# CacheMakerUno.net
KiCad netlist of a schematic drawn in EAGLE
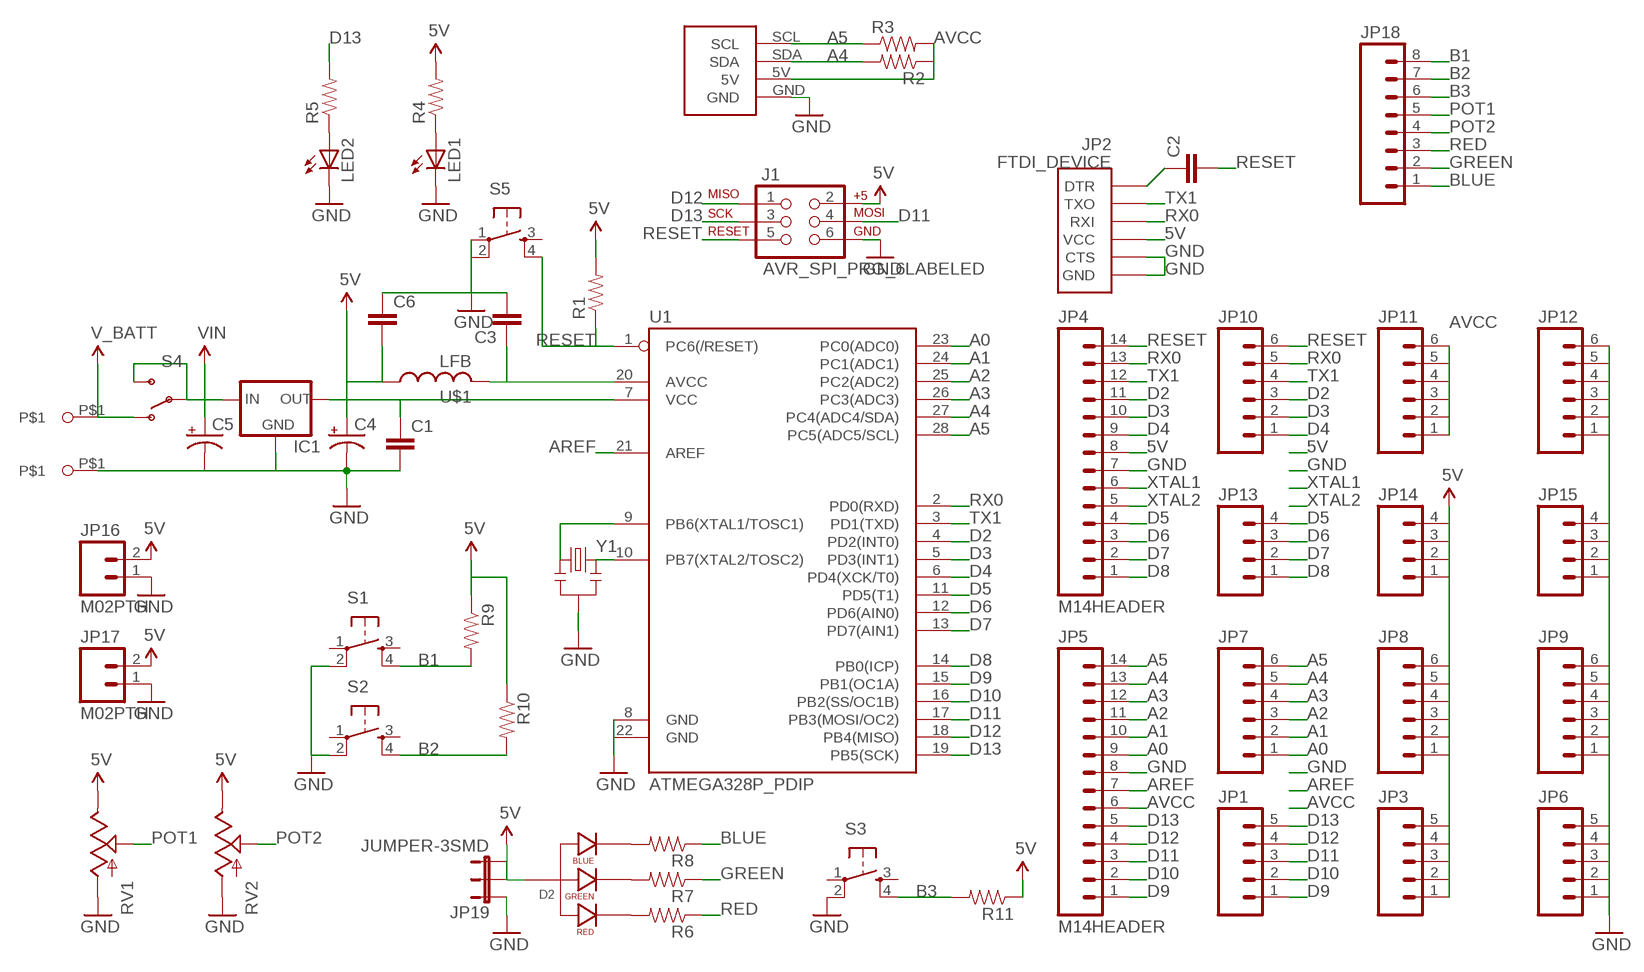
[diagram p0: schematic, sheet 1]

(export (version "E")
  (design (tool "Eeschema 10.0.6"))
  (components
    (comp (ref "C1")
      (value "CAPPTH")
      (footprint "eagle-import:CAP-PTH-SMALL")
      (libsource (lib "eagle-import") (part "CAPPTH"))
    )
    (comp (ref "C2")
      (value "CAPPTH")
      (footprint "eagle-import:CAP-PTH-SMALL")
      (libsource (lib "eagle-import") (part "CAPPTH"))
    )
    (comp (ref "C3")
      (value "CAPPTH")
      (footprint "eagle-import:CAP-PTH-SMALL")
      (libsource (lib "eagle-import") (part "CAPPTH"))
    )
    (comp (ref "C4")
      (value "CAP_POL2MM")
      (footprint "eagle-import:CAP-PTH-2MM")
      (libsource (lib "eagle-import") (part "CAP_POL2MM"))
    )
    (comp (ref "C5")
      (value "CAP_POL2MM")
      (footprint "eagle-import:CAP-PTH-2MM")
      (libsource (lib "eagle-import") (part "CAP_POL2MM"))
    )
    (comp (ref "C6")
      (value "CAPPTH")
      (footprint "eagle-import:CAP-PTH-SMALL")
      (libsource (lib "eagle-import") (part "CAPPTH"))
    )
    (comp (ref "D2")
      (value "LED-RGB-CA-THRUDIFFUSE")
      (footprint "eagle-import:LED-RGB-THRU")
      (libsource (lib "eagle-import") (part "LED-RGB-CA-THRUDIFFUSE"))
    )
    (comp (ref "GND")
      (value "M1")
      (footprint "eagle-import:M1_NO_STRAIN")
      (libsource (lib "eagle-import") (part "M1"))
    )
    (comp (ref "IC1")
      (value "V_REG_78XXBASIC")
      (footprint "eagle-import:TO-220-REG-BASIC")
      (libsource (lib "eagle-import") (part "V_REG_78XXBASIC"))
    )
    (comp (ref "J1")
      (value "AVR_SPI_PRG_6LABELED")
      (footprint "eagle-import:2X3-NS")
      (libsource (lib "eagle-import") (part "AVR_SPI_PRG_6LABELED"))
    )
    (comp (ref "JP1")
      (value "M05NO_SILK")
      (footprint "eagle-import:1X05_NO_SILK")
      (libsource (lib "eagle-import") (part "M05NO_SILK"))
    )
    (comp (ref "JP2")
      (value "FTDI_DEVICE")
      (footprint "eagle-import:FTDI_DEVICE_SIDE")
      (libsource (lib "eagle-import") (part "FTDI_DEVICE"))
    )
    (comp (ref "JP3")
      (value "M05NO_SILK")
      (footprint "eagle-import:1X05_NO_SILK")
      (libsource (lib "eagle-import") (part "M05NO_SILK"))
    )
    (comp (ref "JP4")
      (value "M14HEADER")
      (footprint "eagle-import:1X14-HEADER")
      (libsource (lib "eagle-import") (part "M14HEADER"))
    )
    (comp (ref "JP5")
      (value "M14HEADER")
      (footprint "eagle-import:1X14-HEADER")
      (libsource (lib "eagle-import") (part "M14HEADER"))
    )
    (comp (ref "JP6")
      (value "M05NO_SILK")
      (footprint "eagle-import:1X05_NO_SILK")
      (libsource (lib "eagle-import") (part "M05NO_SILK"))
    )
    (comp (ref "JP7")
      (value "M06SIP")
      (footprint "eagle-import:1X06")
      (libsource (lib "eagle-import") (part "M06SIP"))
    )
    (comp (ref "JP8")
      (value "M06SIP")
      (footprint "eagle-import:1X06")
      (libsource (lib "eagle-import") (part "M06SIP"))
    )
    (comp (ref "JP9")
      (value "M06SIP")
      (footprint "eagle-import:1X06")
      (libsource (lib "eagle-import") (part "M06SIP"))
    )
    (comp (ref "JP10")
      (value "M06SIP")
      (footprint "eagle-import:1X06")
      (libsource (lib "eagle-import") (part "M06SIP"))
    )
    (comp (ref "JP11")
      (value "M06SIP")
      (footprint "eagle-import:1X06")
      (libsource (lib "eagle-import") (part "M06SIP"))
    )
    (comp (ref "JP12")
      (value "M06SIP")
      (footprint "eagle-import:1X06")
      (libsource (lib "eagle-import") (part "M06SIP"))
    )
    (comp (ref "JP13")
      (value "M04PTH")
      (footprint "eagle-import:1X04")
      (libsource (lib "eagle-import") (part "M04PTH"))
    )
    (comp (ref "JP14")
      (value "M04PTH")
      (footprint "eagle-import:1X04")
      (libsource (lib "eagle-import") (part "M04PTH"))
    )
    (comp (ref "JP15")
      (value "M04PTH")
      (footprint "eagle-import:1X04")
      (libsource (lib "eagle-import") (part "M04PTH"))
    )
    (comp (ref "JP16")
      (value "M02PTH")
      (footprint "eagle-import:1X02")
      (libsource (lib "eagle-import") (part "M02PTH"))
    )
    (comp (ref "JP17")
      (value "M02PTH")
      (footprint "eagle-import:1X02")
      (libsource (lib "eagle-import") (part "M02PTH"))
    )
    (comp (ref "JP18")
      (value "M081X08")
      (footprint "eagle-import:1X08")
      (libsource (lib "eagle-import") (part "M081X08"))
    )
    (comp (ref "JP19")
      (value "JUMPER-3SMD")
      (footprint "eagle-import:SJ_3")
      (libsource (lib "eagle-import") (part "JUMPER-3SMD"))
    )
    (comp (ref "LED1")
      (value "LED5MM")
      (footprint "eagle-import:LED5MM")
      (libsource (lib "eagle-import") (part "LED5MM"))
    )
    (comp (ref "LED2")
      (value "LED5MM")
      (footprint "eagle-import:LED5MM")
      (libsource (lib "eagle-import") (part "LED5MM"))
    )
    (comp (ref "R1")
      (value "RESISTORAXIAL-0.3")
      (footprint "eagle-import:AXIAL-0.3")
      (libsource (lib "eagle-import") (part "RESISTORAXIAL-0.3"))
    )
    (comp (ref "R2")
      (value "RESISTORAXIAL-0.3")
      (footprint "eagle-import:AXIAL-0.3")
      (libsource (lib "eagle-import") (part "RESISTORAXIAL-0.3"))
    )
    (comp (ref "R3")
      (value "RESISTORAXIAL-0.3")
      (footprint "eagle-import:AXIAL-0.3")
      (libsource (lib "eagle-import") (part "RESISTORAXIAL-0.3"))
    )
    (comp (ref "R4")
      (value "RESISTORPTH-1/4W-VERT")
      (footprint "eagle-import:AXIAL-0.1")
      (libsource (lib "eagle-import") (part "RESISTORPTH-1/4W-VERT"))
    )
    (comp (ref "R5")
      (value "RESISTORAXIAL-0.3")
      (footprint "eagle-import:AXIAL-0.3")
      (libsource (lib "eagle-import") (part "RESISTORAXIAL-0.3"))
    )
    (comp (ref "R6")
      (value "RESISTORPTH-1/4W-VERT")
      (footprint "eagle-import:AXIAL-0.1")
      (libsource (lib "eagle-import") (part "RESISTORPTH-1/4W-VERT"))
    )
    (comp (ref "R7")
      (value "RESISTORPTH-1/4W-VERT")
      (footprint "eagle-import:AXIAL-0.1")
      (libsource (lib "eagle-import") (part "RESISTORPTH-1/4W-VERT"))
    )
    (comp (ref "R8")
      (value "RESISTORPTH-1/4W-VERT")
      (footprint "eagle-import:AXIAL-0.1")
      (libsource (lib "eagle-import") (part "RESISTORPTH-1/4W-VERT"))
    )
    (comp (ref "R9")
      (value "RESISTORPTH-1/4W-VERT")
      (footprint "eagle-import:AXIAL-0.1")
      (libsource (lib "eagle-import") (part "RESISTORPTH-1/4W-VERT"))
    )
    (comp (ref "R10")
      (value "RESISTORPTH-1/4W-VERT")
      (footprint "eagle-import:AXIAL-0.1")
      (libsource (lib "eagle-import") (part "RESISTORPTH-1/4W-VERT"))
    )
    (comp (ref "R11")
      (value "RESISTORPTH-1/4W-VERT")
      (footprint "eagle-import:AXIAL-0.1")
      (libsource (lib "eagle-import") (part "RESISTORPTH-1/4W-VERT"))
    )
    (comp (ref "RV1")
      (value "POTTRIM")
      (footprint "eagle-import:TRIM_POT")
      (libsource (lib "eagle-import") (part "POTTRIM"))
    )
    (comp (ref "RV2")
      (value "POTTRIM")
      (footprint "eagle-import:TRIM_POT")
      (libsource (lib "eagle-import") (part "POTTRIM"))
    )
    (comp (ref "S1")
      (value "TAC_SWITCHPTH")
      (footprint "eagle-import:TACTILE-PTH")
      (libsource (lib "eagle-import") (part "TAC_SWITCHPTH"))
    )
    (comp (ref "S2")
      (value "TAC_SWITCHPTH")
      (footprint "eagle-import:TACTILE-PTH")
      (libsource (lib "eagle-import") (part "TAC_SWITCHPTH"))
    )
    (comp (ref "S3")
      (value "TAC_SWITCHPTH")
      (footprint "eagle-import:TACTILE-PTH")
      (libsource (lib "eagle-import") (part "TAC_SWITCHPTH"))
    )
    (comp (ref "S4")
      (value "SWITCH-SPDTPTH")
      (footprint "eagle-import:SWITCH-SPDT")
      (libsource (lib "eagle-import") (part "SWITCH-SPDTPTH"))
    )
    (comp (ref "S5")
      (value "TAC_SWITCHPTH")
      (footprint "eagle-import:TACTILE-PTH")
      (libsource (lib "eagle-import") (part "TAC_SWITCHPTH"))
    )
    (comp (ref "U$1")
      (value "LFB")
      (footprint "eagle-import:ALFB-01")
      (libsource (lib "eagle-import") (part "LFB"))
    )
    (comp (ref "U$2")
      (value "I2C")
      (footprint "eagle-import:I2C")
      (libsource (lib "eagle-import") (part "I2C"))
    )
    (comp (ref "U1")
      (value "ATMEGA328P_PDIP")
      (footprint "eagle-import:DIL28-3")
      (libsource (lib "eagle-import") (part "ATMEGA328P_PDIP"))
    )
    (comp (ref "V+")
      (value "M1")
      (footprint "eagle-import:M1_NO_STRAIN")
      (libsource (lib "eagle-import") (part "M1"))
    )
    (comp (ref "Y1")
      (value "RESONATORPTH")
      (footprint "eagle-import:RESONATOR-PTH")
      (libsource (lib "eagle-import") (part "RESONATORPTH"))
    )
  )
  (nets
    (net (code "1") (name "/A0") (class "Default")
      (node (ref "JP5") (pin "9") (pinfunction "9_9") (pintype "passive"))
      (node (ref "JP7") (pin "1") (pinfunction "1_1") (pintype "passive"))
      (node (ref "U1") (pin "23") (pinfunction "PC0(ADC0)_23") (pintype "bidirectional"))
    )
    (net (code "2") (name "/A1") (class "Default")
      (node (ref "JP5") (pin "10") (pinfunction "10_10") (pintype "passive"))
      (node (ref "JP7") (pin "2") (pinfunction "2_2") (pintype "passive"))
      (node (ref "U1") (pin "24") (pinfunction "PC1(ADC1)_24") (pintype "bidirectional"))
    )
    (net (code "3") (name "/A2") (class "Default")
      (node (ref "JP5") (pin "11") (pinfunction "11_11") (pintype "passive"))
      (node (ref "JP7") (pin "3") (pinfunction "3_3") (pintype "passive"))
      (node (ref "U1") (pin "25") (pinfunction "PC2(ADC2)_25") (pintype "bidirectional"))
    )
    (net (code "4") (name "/A3") (class "Default")
      (node (ref "JP5") (pin "12") (pinfunction "12_12") (pintype "passive"))
      (node (ref "JP7") (pin "4") (pinfunction "4_4") (pintype "passive"))
      (node (ref "U1") (pin "26") (pinfunction "PC3(ADC3)_26") (pintype "bidirectional"))
    )
    (net (code "5") (name "/A4") (class "Default")
      (node (ref "JP5") (pin "13") (pinfunction "13_13") (pintype "passive"))
      (node (ref "JP7") (pin "5") (pinfunction "5_5") (pintype "passive"))
      (node (ref "R2") (pin "P$2") (pinfunction "2_P$2") (pintype "passive"))
      (node (ref "U$2") (pin "SDA") (pinfunction "SDA_SDA") (pintype "bidirectional"))
      (node (ref "U1") (pin "27") (pinfunction "PC4(ADC4/SDA)_27") (pintype "bidirectional"))
    )
    (net (code "6") (name "/A5") (class "Default")
      (node (ref "JP5") (pin "14") (pinfunction "14_14") (pintype "passive"))
      (node (ref "JP7") (pin "6") (pinfunction "6_6") (pintype "passive"))
      (node (ref "R3") (pin "P$1") (pinfunction "1_P$1") (pintype "passive"))
      (node (ref "U$2") (pin "SCL") (pinfunction "SCL_SCL") (pintype "bidirectional"))
      (node (ref "U1") (pin "28") (pinfunction "PC5(ADC5/SCL)_28") (pintype "bidirectional"))
    )
    (net (code "7") (name "/AREF") (class "Default")
      (node (ref "JP5") (pin "7") (pinfunction "7_7") (pintype "passive"))
      (node (ref "U1") (pin "21") (pinfunction "AREF_21") (pintype "bidirectional"))
    )
    (net (code "8") (name "/AVCC") (class "Default")
      (node (ref "C3") (pin "1") (pinfunction "1_1") (pintype "passive"))
      (node (ref "JP11") (pin "1") (pinfunction "1_1") (pintype "passive"))
      (node (ref "JP11") (pin "2") (pinfunction "2_2") (pintype "passive"))
      (node (ref "JP11") (pin "3") (pinfunction "3_3") (pintype "passive"))
      (node (ref "JP11") (pin "4") (pinfunction "4_4") (pintype "passive"))
      (node (ref "JP11") (pin "5") (pinfunction "5_5") (pintype "passive"))
      (node (ref "JP11") (pin "6") (pinfunction "6_6") (pintype "passive"))
      (node (ref "JP5") (pin "6") (pinfunction "6_6") (pintype "passive"))
      (node (ref "R2") (pin "P$1") (pinfunction "1_P$1") (pintype "passive"))
      (node (ref "R3") (pin "P$2") (pinfunction "2_P$2") (pintype "passive"))
      (node (ref "U$1") (pin "2") (pinfunction "2_2") (pintype "passive"))
      (node (ref "U$2") (pin "5V") (pinfunction "5V_5V") (pintype "bidirectional"))
      (node (ref "U1") (pin "20") (pinfunction "AVCC_20") (pintype "bidirectional"))
    )
    (net (code "9") (name "/B1") (class "Default")
      (node (ref "JP18") (pin "8") (pinfunction "8_8") (pintype "passive"))
      (node (ref "R9") (pin "P$2") (pinfunction "2_P$2") (pintype "passive"))
      (node (ref "S1") (pin "4") (pinfunction "4_4") (pintype "passive"))
    )
    (net (code "10") (name "/B2") (class "Default")
      (node (ref "JP18") (pin "7") (pinfunction "7_7") (pintype "passive"))
      (node (ref "R10") (pin "P$2") (pinfunction "2_P$2") (pintype "passive"))
      (node (ref "S2") (pin "4") (pinfunction "4_4") (pintype "passive"))
    )
    (net (code "11") (name "/B3") (class "Default")
      (node (ref "JP18") (pin "6") (pinfunction "6_6") (pintype "passive"))
      (node (ref "R11") (pin "P$2") (pinfunction "2_P$2") (pintype "passive"))
      (node (ref "S3") (pin "4") (pinfunction "4_4") (pintype "passive"))
    )
    (net (code "12") (name "/BLUE") (class "Default")
      (node (ref "JP18") (pin "1") (pinfunction "1_1") (pintype "passive"))
      (node (ref "R8") (pin "P$1") (pinfunction "1_P$1") (pintype "passive"))
    )
    (net (code "13") (name "/D2") (class "Default")
      (node (ref "JP10") (pin "3") (pinfunction "3_3") (pintype "passive"))
      (node (ref "JP4") (pin "11") (pinfunction "11_11") (pintype "passive"))
      (node (ref "U1") (pin "4") (pinfunction "PD2(INT0)_4") (pintype "bidirectional"))
    )
    (net (code "14") (name "/D3") (class "Default")
      (node (ref "JP10") (pin "2") (pinfunction "2_2") (pintype "passive"))
      (node (ref "JP4") (pin "10") (pinfunction "10_10") (pintype "passive"))
      (node (ref "U1") (pin "5") (pinfunction "PD3(INT1)_5") (pintype "bidirectional"))
    )
    (net (code "15") (name "/D4") (class "Default")
      (node (ref "JP10") (pin "1") (pinfunction "1_1") (pintype "passive"))
      (node (ref "JP4") (pin "9") (pinfunction "9_9") (pintype "passive"))
      (node (ref "U1") (pin "6") (pinfunction "PD4(XCK/T0)_6") (pintype "bidirectional"))
    )
    (net (code "16") (name "/D5") (class "Default")
      (node (ref "JP13") (pin "4") (pinfunction "4_4") (pintype "passive"))
      (node (ref "JP4") (pin "4") (pinfunction "4_4") (pintype "passive"))
      (node (ref "U1") (pin "11") (pinfunction "PD5(T1)_11") (pintype "bidirectional"))
    )
    (net (code "17") (name "/D6") (class "Default")
      (node (ref "JP13") (pin "3") (pinfunction "3_3") (pintype "passive"))
      (node (ref "JP4") (pin "3") (pinfunction "3_3") (pintype "passive"))
      (node (ref "U1") (pin "12") (pinfunction "PD6(AIN0)_12") (pintype "bidirectional"))
    )
    (net (code "18") (name "/D7") (class "Default")
      (node (ref "JP13") (pin "2") (pinfunction "2_2") (pintype "passive"))
      (node (ref "JP4") (pin "2") (pinfunction "2_2") (pintype "passive"))
      (node (ref "U1") (pin "13") (pinfunction "PD7(AIN1)_13") (pintype "bidirectional"))
    )
    (net (code "19") (name "/D8") (class "Default")
      (node (ref "JP13") (pin "1") (pinfunction "1_1") (pintype "passive"))
      (node (ref "JP4") (pin "1") (pinfunction "1_1") (pintype "passive"))
      (node (ref "U1") (pin "14") (pinfunction "PB0(ICP)_14") (pintype "bidirectional"))
    )
    (net (code "20") (name "/D9") (class "Default")
      (node (ref "JP1") (pin "1") (pinfunction "1_1") (pintype "passive"))
      (node (ref "JP5") (pin "1") (pinfunction "1_1") (pintype "passive"))
      (node (ref "U1") (pin "15") (pinfunction "PB1(OC1A)_15") (pintype "bidirectional"))
    )
    (net (code "21") (name "/D10") (class "Default")
      (node (ref "JP1") (pin "2") (pinfunction "2_2") (pintype "passive"))
      (node (ref "JP5") (pin "2") (pinfunction "2_2") (pintype "passive"))
      (node (ref "U1") (pin "16") (pinfunction "PB2(SS/OC1B)_16") (pintype "bidirectional"))
    )
    (net (code "22") (name "/D11") (class "Default")
      (node (ref "J1") (pin "4") (pinfunction "4_4") (pintype "passive"))
      (node (ref "JP1") (pin "3") (pinfunction "3_3") (pintype "passive"))
      (node (ref "JP5") (pin "3") (pinfunction "3_3") (pintype "passive"))
      (node (ref "U1") (pin "17") (pinfunction "PB3(MOSI/OC2)_17") (pintype "bidirectional"))
    )
    (net (code "23") (name "/D12") (class "Default")
      (node (ref "J1") (pin "1") (pinfunction "1_1") (pintype "passive"))
      (node (ref "JP1") (pin "4") (pinfunction "4_4") (pintype "passive"))
      (node (ref "JP5") (pin "4") (pinfunction "4_4") (pintype "passive"))
      (node (ref "U1") (pin "18") (pinfunction "PB4(MISO)_18") (pintype "bidirectional"))
    )
    (net (code "24") (name "/D13") (class "Default")
      (node (ref "J1") (pin "3") (pinfunction "3_3") (pintype "passive"))
      (node (ref "JP1") (pin "5") (pinfunction "5_5") (pintype "passive"))
      (node (ref "JP5") (pin "5") (pinfunction "5_5") (pintype "passive"))
      (node (ref "R5") (pin "P$2") (pinfunction "2_P$2") (pintype "passive"))
      (node (ref "U1") (pin "19") (pinfunction "PB5(SCK)_19") (pintype "bidirectional"))
    )
    (net (code "25") (name "/GREEN") (class "Default")
      (node (ref "JP18") (pin "2") (pinfunction "2_2") (pintype "passive"))
      (node (ref "R7") (pin "P$1") (pinfunction "1_P$1") (pintype "passive"))
    )
    (net (code "26") (name "/POT1") (class "Default")
      (node (ref "JP18") (pin "5") (pinfunction "5_5") (pintype "passive"))
      (node (ref "RV1") (pin "1") (pinfunction "S_1") (pintype "passive"))
    )
    (net (code "27") (name "/POT2") (class "Default")
      (node (ref "JP18") (pin "4") (pinfunction "4_4") (pintype "passive"))
      (node (ref "RV2") (pin "1") (pinfunction "S_1") (pintype "passive"))
    )
    (net (code "28") (name "/RED") (class "Default")
      (node (ref "JP18") (pin "3") (pinfunction "3_3") (pintype "passive"))
      (node (ref "R6") (pin "P$1") (pinfunction "1_P$1") (pintype "passive"))
    )
    (net (code "29") (name "/RESET") (class "Default")
      (node (ref "C2") (pin "2") (pinfunction "2_2") (pintype "passive"))
      (node (ref "J1") (pin "5") (pinfunction "5_5") (pintype "passive"))
      (node (ref "JP10") (pin "6") (pinfunction "6_6") (pintype "passive"))
      (node (ref "JP4") (pin "14") (pinfunction "14_14") (pintype "passive"))
      (node (ref "R1") (pin "P$1") (pinfunction "1_P$1") (pintype "passive"))
      (node (ref "S5") (pin "4") (pinfunction "4_4") (pintype "passive"))
      (node (ref "U1") (pin "1") (pinfunction "PC6(/RESET)_1") (pintype "bidirectional"))
    )
    (net (code "30") (name "/RX0") (class "Default")
      (node (ref "JP10") (pin "5") (pinfunction "5_5") (pintype "passive"))
      (node (ref "JP2") (pin "P$3") (pinfunction "RXI_P$3") (pintype "bidirectional"))
      (node (ref "JP4") (pin "13") (pinfunction "13_13") (pintype "passive"))
      (node (ref "U1") (pin "2") (pinfunction "PD0(RXD)_2") (pintype "bidirectional"))
    )
    (net (code "31") (name "/TX1") (class "Default")
      (node (ref "JP10") (pin "4") (pinfunction "4_4") (pintype "passive"))
      (node (ref "JP2") (pin "P$2") (pinfunction "TXO_P$2") (pintype "bidirectional"))
      (node (ref "JP4") (pin "12") (pinfunction "12_12") (pintype "passive"))
      (node (ref "U1") (pin "3") (pinfunction "PD1(TXD)_3") (pintype "bidirectional"))
    )
    (net (code "32") (name "/XTAL1") (class "Default")
      (node (ref "JP4") (pin "6") (pinfunction "6_6") (pintype "passive"))
      (node (ref "U1") (pin "9") (pinfunction "PB6(XTAL1/TOSC1)_9") (pintype "bidirectional"))
      (node (ref "Y1") (pin "1") (pinfunction "1_1") (pintype "passive"))
    )
    (net (code "33") (name "/XTAL2") (class "Default")
      (node (ref "JP4") (pin "5") (pinfunction "5_5") (pintype "passive"))
      (node (ref "U1") (pin "10") (pinfunction "PB7(XTAL2/TOSC2)_10") (pintype "bidirectional"))
      (node (ref "Y1") (pin "3") (pinfunction "3_3") (pintype "passive"))
    )
    (net (code "34") (name "5V") (class "Default")
      (node (ref "C1") (pin "1") (pinfunction "1_1") (pintype "passive"))
      (node (ref "C4") (pin "+") (pinfunction "+_+") (pintype "passive"))
      (node (ref "C6") (pin "2") (pinfunction "2_2") (pintype "passive"))
      (node (ref "D2") (pin "2") (pinfunction "ANODE_2") (pintype "bidirectional"))
      (node (ref "IC1") (pin "3") (pinfunction "OUT_3") (pintype "output"))
      (node (ref "J1") (pin "2") (pinfunction "2_2") (pintype "passive"))
      (node (ref "JP14") (pin "1") (pinfunction "1_1") (pintype "passive"))
      (node (ref "JP14") (pin "2") (pinfunction "2_2") (pintype "passive"))
      (node (ref "JP14") (pin "3") (pinfunction "3_3") (pintype "passive"))
      (node (ref "JP14") (pin "4") (pinfunction "4_4") (pintype "passive"))
      (node (ref "JP16") (pin "2") (pinfunction "2_2") (pintype "passive"))
      (node (ref "JP17") (pin "2") (pinfunction "2_2") (pintype "passive"))
      (node (ref "JP19") (pin "2") (pinfunction "2_2") (pintype "passive"))
      (node (ref "JP19") (pin "3") (pinfunction "3_3") (pintype "passive"))
      (node (ref "JP2") (pin "P$4") (pinfunction "VCC_P$4") (pintype "bidirectional"))
      (node (ref "JP3") (pin "1") (pinfunction "1_1") (pintype "passive"))
      (node (ref "JP3") (pin "2") (pinfunction "2_2") (pintype "passive"))
      (node (ref "JP3") (pin "3") (pinfunction "3_3") (pintype "passive"))
      (node (ref "JP3") (pin "4") (pinfunction "4_4") (pintype "passive"))
      (node (ref "JP3") (pin "5") (pinfunction "5_5") (pintype "passive"))
      (node (ref "JP4") (pin "8") (pinfunction "8_8") (pintype "passive"))
      (node (ref "JP8") (pin "1") (pinfunction "1_1") (pintype "passive"))
      (node (ref "JP8") (pin "2") (pinfunction "2_2") (pintype "passive"))
      (node (ref "JP8") (pin "3") (pinfunction "3_3") (pintype "passive"))
      (node (ref "JP8") (pin "4") (pinfunction "4_4") (pintype "passive"))
      (node (ref "JP8") (pin "5") (pinfunction "5_5") (pintype "passive"))
      (node (ref "JP8") (pin "6") (pinfunction "6_6") (pintype "passive"))
      (node (ref "R1") (pin "P$2") (pinfunction "2_P$2") (pintype "passive"))
      (node (ref "R10") (pin "P$1") (pinfunction "1_P$1") (pintype "passive"))
      (node (ref "R11") (pin "P$1") (pinfunction "1_P$1") (pintype "passive"))
      (node (ref "R4") (pin "P$2") (pinfunction "2_P$2") (pintype "passive"))
      (node (ref "R9") (pin "P$1") (pinfunction "1_P$1") (pintype "passive"))
      (node (ref "RV1") (pin "2") (pinfunction "E_2") (pintype "passive"))
      (node (ref "RV2") (pin "2") (pinfunction "E_2") (pintype "passive"))
      (node (ref "U$1") (pin "1") (pinfunction "1_1") (pintype "passive"))
      (node (ref "U1") (pin "7") (pinfunction "VCC_7") (pintype "bidirectional"))
    )
    (net (code "35") (name "GND") (class "Default")
      (node (ref "C1") (pin "2") (pinfunction "2_2") (pintype "passive"))
      (node (ref "C3") (pin "2") (pinfunction "2_2") (pintype "passive"))
      (node (ref "C4") (pin "-") (pinfunction "-_-") (pintype "passive"))
      (node (ref "C5") (pin "-") (pinfunction "-_-") (pintype "passive"))
      (node (ref "C6") (pin "1") (pinfunction "1_1") (pintype "passive"))
      (node (ref "GND") (pin "P$1") (pinfunction "P$1_P$1") (pintype "bidirectional"))
      (node (ref "IC1") (pin "2") (pinfunction "GND_2") (pintype "input"))
      (node (ref "J1") (pin "6") (pinfunction "6_6") (pintype "passive"))
      (node (ref "JP12") (pin "1") (pinfunction "1_1") (pintype "passive"))
      (node (ref "JP12") (pin "2") (pinfunction "2_2") (pintype "passive"))
      (node (ref "JP12") (pin "3") (pinfunction "3_3") (pintype "passive"))
      (node (ref "JP12") (pin "4") (pinfunction "4_4") (pintype "passive"))
      (node (ref "JP12") (pin "5") (pinfunction "5_5") (pintype "passive"))
      (node (ref "JP12") (pin "6") (pinfunction "6_6") (pintype "passive"))
      (node (ref "JP15") (pin "1") (pinfunction "1_1") (pintype "passive"))
      (node (ref "JP15") (pin "2") (pinfunction "2_2") (pintype "passive"))
      (node (ref "JP15") (pin "3") (pinfunction "3_3") (pintype "passive"))
      (node (ref "JP15") (pin "4") (pinfunction "4_4") (pintype "passive"))
      (node (ref "JP16") (pin "1") (pinfunction "1_1") (pintype "passive"))
      (node (ref "JP17") (pin "1") (pinfunction "1_1") (pintype "passive"))
      (node (ref "JP19") (pin "1") (pinfunction "1_1") (pintype "passive"))
      (node (ref "JP2") (pin "P$5") (pinfunction "CTS_P$5") (pintype "bidirectional"))
      (node (ref "JP2") (pin "P$6") (pinfunction "GND_P$6") (pintype "bidirectional"))
      (node (ref "JP4") (pin "7") (pinfunction "7_7") (pintype "passive"))
      (node (ref "JP5") (pin "8") (pinfunction "8_8") (pintype "passive"))
      (node (ref "JP6") (pin "1") (pinfunction "1_1") (pintype "passive"))
      (node (ref "JP6") (pin "2") (pinfunction "2_2") (pintype "passive"))
      (node (ref "JP6") (pin "3") (pinfunction "3_3") (pintype "passive"))
      (node (ref "JP6") (pin "4") (pinfunction "4_4") (pintype "passive"))
      (node (ref "JP6") (pin "5") (pinfunction "5_5") (pintype "passive"))
      (node (ref "JP9") (pin "1") (pinfunction "1_1") (pintype "passive"))
      (node (ref "JP9") (pin "2") (pinfunction "2_2") (pintype "passive"))
      (node (ref "JP9") (pin "3") (pinfunction "3_3") (pintype "passive"))
      (node (ref "JP9") (pin "4") (pinfunction "4_4") (pintype "passive"))
      (node (ref "JP9") (pin "5") (pinfunction "5_5") (pintype "passive"))
      (node (ref "JP9") (pin "6") (pinfunction "6_6") (pintype "passive"))
      (node (ref "LED1") (pin "K") (pinfunction "C_K") (pintype "passive"))
      (node (ref "LED2") (pin "K") (pinfunction "C_K") (pintype "passive"))
      (node (ref "RV1") (pin "3") (pinfunction "A_3") (pintype "passive"))
      (node (ref "RV2") (pin "3") (pinfunction "A_3") (pintype "passive"))
      (node (ref "S1") (pin "2") (pinfunction "2_2") (pintype "passive"))
      (node (ref "S2") (pin "2") (pinfunction "2_2") (pintype "passive"))
      (node (ref "S3") (pin "2") (pinfunction "2_2") (pintype "passive"))
      (node (ref "S5") (pin "1") (pinfunction "1_1") (pintype "passive"))
      (node (ref "S5") (pin "2") (pinfunction "2_2") (pintype "passive"))
      (node (ref "U$2") (pin "GND") (pinfunction "GND_GND") (pintype "bidirectional"))
      (node (ref "U1") (pin "22") (pinfunction "GND_22") (pintype "bidirectional"))
      (node (ref "U1") (pin "8") (pinfunction "GND_8") (pintype "bidirectional"))
      (node (ref "Y1") (pin "2") (pinfunction "2_2") (pintype "passive"))
    )
    (net (code "36") (name "Net-(D2-BLUE_CATHODE)") (class "Default")
      (node (ref "D2") (pin "4") (pinfunction "BLUE_CATHODE_4") (pintype "bidirectional"))
      (node (ref "R8") (pin "P$2") (pinfunction "2_P$2") (pintype "passive"))
    )
    (net (code "37") (name "Net-(D2-GREEN_CATHODE)") (class "Default")
      (node (ref "D2") (pin "3") (pinfunction "GREEN_CATHODE_3") (pintype "bidirectional"))
      (node (ref "R7") (pin "P$2") (pinfunction "2_P$2") (pintype "passive"))
    )
    (net (code "38") (name "Net-(D2-RED_CATHODE)") (class "Default")
      (node (ref "D2") (pin "1") (pinfunction "RED_CATHODE_1") (pintype "bidirectional"))
      (node (ref "R6") (pin "P$2") (pinfunction "2_P$2") (pintype "passive"))
    )
    (net (code "39") (name "Net-(JP2-DTR)") (class "Default")
      (node (ref "C2") (pin "1") (pinfunction "1_1") (pintype "passive"))
      (node (ref "JP2") (pin "P$1") (pinfunction "DTR_P$1") (pintype "bidirectional"))
    )
    (net (code "40") (name "Net-(R4-1)") (class "Default")
      (node (ref "LED1") (pin "A") (pinfunction "A_A") (pintype "passive"))
      (node (ref "R4") (pin "P$1") (pinfunction "1_P$1") (pintype "passive"))
    )
    (net (code "41") (name "Net-(R5-1)") (class "Default")
      (node (ref "LED2") (pin "A") (pinfunction "A_A") (pintype "passive"))
      (node (ref "R5") (pin "P$1") (pinfunction "1_P$1") (pintype "passive"))
    )
    (net (code "42") (name "VIN") (class "Default")
      (node (ref "C5") (pin "+") (pinfunction "+_+") (pintype "passive"))
      (node (ref "IC1") (pin "1") (pinfunction "IN_1") (pintype "input"))
      (node (ref "S4") (pin "2") (pinfunction "P_2") (pintype "passive"))
      (node (ref "S4") (pin "3") (pinfunction "S_3") (pintype "passive"))
    )
    (net (code "43") (name "V_BATT") (class "Default")
      (node (ref "S4") (pin "1") (pinfunction "O_1") (pintype "passive"))
      (node (ref "V+") (pin "P$1") (pinfunction "P$1_P$1") (pintype "bidirectional"))
    )
    (net (code "44") (name "unconnected-(S1-Pad1)") (class "Default")
      (node (ref "S1") (pin "1") (pinfunction "1_1") (pintype "passive"))
    )
    (net (code "45") (name "unconnected-(S1-Pad3)") (class "Default")
      (node (ref "S1") (pin "3") (pinfunction "3_3") (pintype "passive"))
    )
    (net (code "46") (name "unconnected-(S2-Pad1)") (class "Default")
      (node (ref "S2") (pin "1") (pinfunction "1_1") (pintype "passive"))
    )
    (net (code "47") (name "unconnected-(S2-Pad3)") (class "Default")
      (node (ref "S2") (pin "3") (pinfunction "3_3") (pintype "passive"))
    )
    (net (code "48") (name "unconnected-(S3-Pad1)") (class "Default")
      (node (ref "S3") (pin "1") (pinfunction "1_1") (pintype "passive"))
    )
    (net (code "49") (name "unconnected-(S3-Pad3)") (class "Default")
      (node (ref "S3") (pin "3") (pinfunction "3_3") (pintype "passive"))
    )
    (net (code "50") (name "unconnected-(S5-Pad3)") (class "Default")
      (node (ref "S5") (pin "3") (pinfunction "3_3") (pintype "passive"))
    )
  )
)
